# rpm.net
KiCad netlist of a schematic drawn in Altium Designer
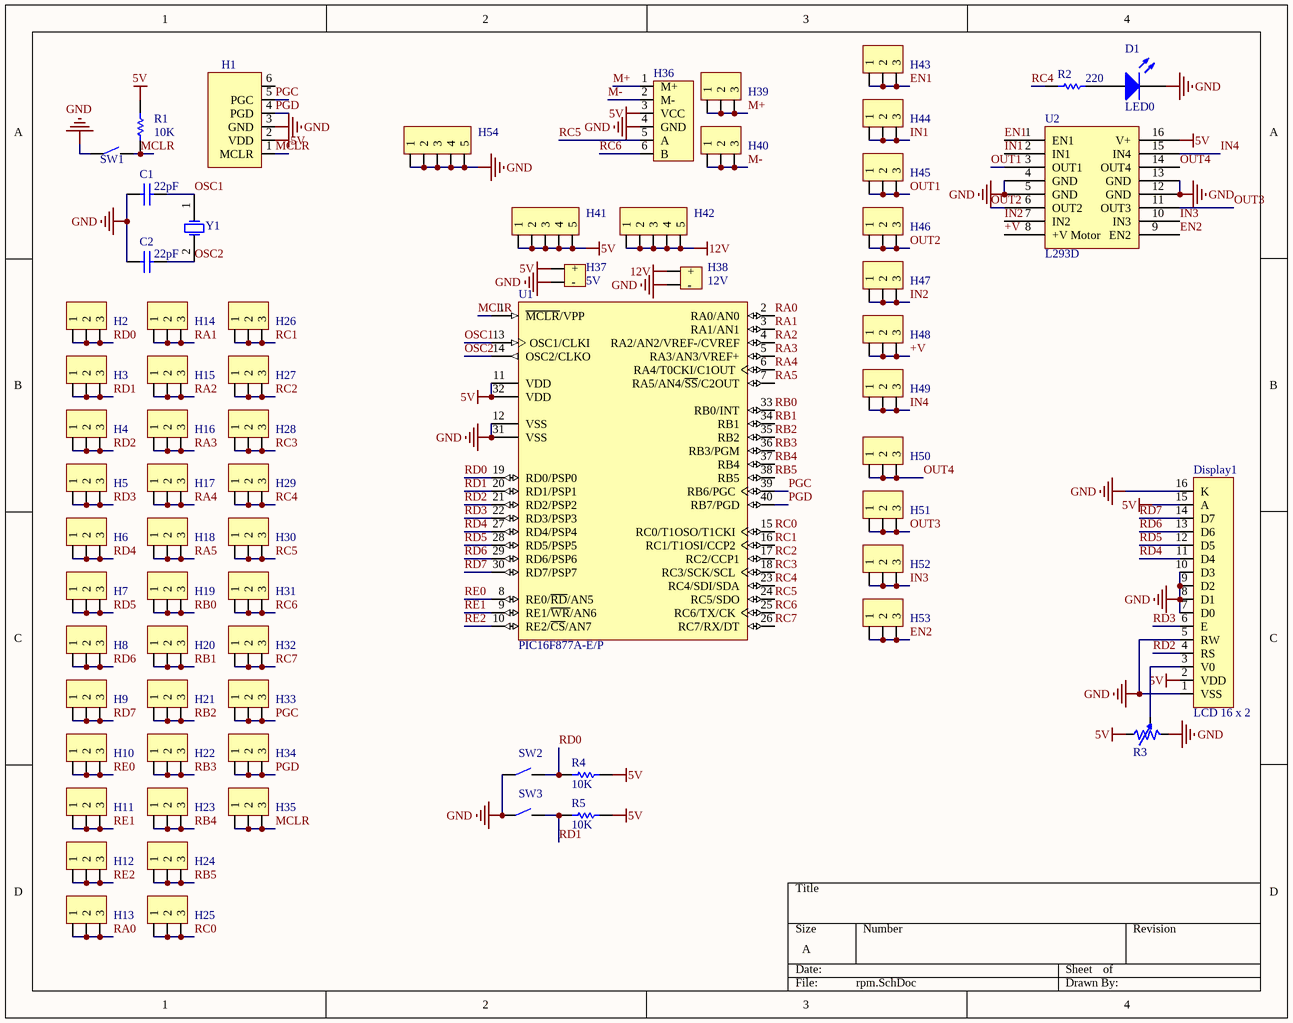
[diagram p0: rpm.SchDoc]

(export (version "E")
  (design (tool "Eeschema 10.0.6"))
  (components
    (comp (ref "C1")
      (value "22pF")
      (footprint "RAD-0.3")
      (description "Capacitor")
      (fields (field (name "Comment") "Cap") (field (name "PUBLISHER") "Altium Limited"))
      (libsource (lib "Miscellaneous Devices") (part "Cap"))
    )
    (comp (ref "C2")
      (value "22pF")
      (footprint "RAD-0.3")
      (description "Capacitor")
      (fields (field (name "Comment") "Cap") (field (name "PUBLISHER") "Altium Limited"))
      (libsource (lib "Miscellaneous Devices") (part "Cap"))
    )
    (comp (ref "D1")
      (value "LED0")
      (footprint "LED-0")
      (description "Typical INFRARED GaAs LED")
      (fields (field (name "PUBLISHER") "Altium Limited"))
      (libsource (lib "Miscellaneous Devices") (part "LED0"))
    )
    (comp (ref "Display1")
      (value "LCD 16 x 2")
      (footprint "LCD16x2")
      (libsource (lib "Konektori") (part "LCD 16 X 2"))
    )
    (comp (ref "H1") (value "Programmer") (footprint "Pickit") (libsource (lib "Konektori") (part "PICKIT")))
    (comp (ref "H2")
      (value "Comment")
      (footprint "1X3 HEADER")
      (libsource (lib "Konektori") (part "1X3 Header"))
    )
    (comp (ref "H3")
      (value "Comment")
      (footprint "1X3 HEADER")
      (libsource (lib "Konektori") (part "1X3 Header"))
    )
    (comp (ref "H4")
      (value "Comment")
      (footprint "1X3 HEADER")
      (libsource (lib "Konektori") (part "1X3 Header"))
    )
    (comp (ref "H5")
      (value "Comment")
      (footprint "1X3 HEADER")
      (libsource (lib "Konektori") (part "1X3 Header"))
    )
    (comp (ref "H6")
      (value "Comment")
      (footprint "1X3 HEADER")
      (libsource (lib "Konektori") (part "1X3 Header"))
    )
    (comp (ref "H7")
      (value "Comment")
      (footprint "1X3 HEADER")
      (libsource (lib "Konektori") (part "1X3 Header"))
    )
    (comp (ref "H8")
      (value "Comment")
      (footprint "1X3 HEADER")
      (libsource (lib "Konektori") (part "1X3 Header"))
    )
    (comp (ref "H9")
      (value "Comment")
      (footprint "1X3 HEADER")
      (libsource (lib "Konektori") (part "1X3 Header"))
    )
    (comp (ref "H10")
      (value "Comment")
      (footprint "1X3 HEADER")
      (libsource (lib "Konektori") (part "1X3 Header"))
    )
    (comp (ref "H11")
      (value "Comment")
      (footprint "1X3 HEADER")
      (libsource (lib "Konektori") (part "1X3 Header"))
    )
    (comp (ref "H12")
      (value "Comment")
      (footprint "1X3 HEADER")
      (libsource (lib "Konektori") (part "1X3 Header"))
    )
    (comp (ref "H13")
      (value "Comment")
      (footprint "1X3 HEADER")
      (libsource (lib "Konektori") (part "1X3 Header"))
    )
    (comp (ref "H14")
      (value "Comment")
      (footprint "1X3 HEADER")
      (libsource (lib "Konektori") (part "1X3 Header"))
    )
    (comp (ref "H15")
      (value "Comment")
      (footprint "1X3 HEADER")
      (libsource (lib "Konektori") (part "1X3 Header"))
    )
    (comp (ref "H16")
      (value "Comment")
      (footprint "1X3 HEADER")
      (libsource (lib "Konektori") (part "1X3 Header"))
    )
    (comp (ref "H17")
      (value "Comment")
      (footprint "1X3 HEADER")
      (libsource (lib "Konektori") (part "1X3 Header"))
    )
    (comp (ref "H18")
      (value "Comment")
      (footprint "1X3 HEADER")
      (libsource (lib "Konektori") (part "1X3 Header"))
    )
    (comp (ref "H19")
      (value "Comment")
      (footprint "1X3 HEADER")
      (libsource (lib "Konektori") (part "1X3 Header"))
    )
    (comp (ref "H20")
      (value "Comment")
      (footprint "1X3 HEADER")
      (libsource (lib "Konektori") (part "1X3 Header"))
    )
    (comp (ref "H21")
      (value "Comment")
      (footprint "1X3 HEADER")
      (libsource (lib "Konektori") (part "1X3 Header"))
    )
    (comp (ref "H22")
      (value "Comment")
      (footprint "1X3 HEADER")
      (libsource (lib "Konektori") (part "1X3 Header"))
    )
    (comp (ref "H23")
      (value "Comment")
      (footprint "1X3 HEADER")
      (libsource (lib "Konektori") (part "1X3 Header"))
    )
    (comp (ref "H24")
      (value "Comment")
      (footprint "1X3 HEADER")
      (libsource (lib "Konektori") (part "1X3 Header"))
    )
    (comp (ref "H25")
      (value "Comment")
      (footprint "1X3 HEADER")
      (libsource (lib "Konektori") (part "1X3 Header"))
    )
    (comp (ref "H26")
      (value "Comment")
      (footprint "1X3 HEADER")
      (libsource (lib "Konektori") (part "1X3 Header"))
    )
    (comp (ref "H27")
      (value "Comment")
      (footprint "1X3 HEADER")
      (libsource (lib "Konektori") (part "1X3 Header"))
    )
    (comp (ref "H28")
      (value "Comment")
      (footprint "1X3 HEADER")
      (libsource (lib "Konektori") (part "1X3 Header"))
    )
    (comp (ref "H29")
      (value "Comment")
      (footprint "1X3 HEADER")
      (libsource (lib "Konektori") (part "1X3 Header"))
    )
    (comp (ref "H30")
      (value "Comment")
      (footprint "1X3 HEADER")
      (libsource (lib "Konektori") (part "1X3 Header"))
    )
    (comp (ref "H31")
      (value "Comment")
      (footprint "1X3 HEADER")
      (libsource (lib "Konektori") (part "1X3 Header"))
    )
    (comp (ref "H32")
      (value "Comment")
      (footprint "1X3 HEADER")
      (libsource (lib "Konektori") (part "1X3 Header"))
    )
    (comp (ref "H33")
      (value "Comment")
      (footprint "1X3 HEADER")
      (libsource (lib "Konektori") (part "1X3 Header"))
    )
    (comp (ref "H34")
      (value "Comment")
      (footprint "1X3 HEADER")
      (libsource (lib "Konektori") (part "1X3 Header"))
    )
    (comp (ref "H35")
      (value "Comment")
      (footprint "1X3 HEADER")
      (libsource (lib "Konektori") (part "1X3 Header"))
    )
    (comp (ref "H36")
      (value "Comment")
      (footprint "MOTOR ENCODER BLUE SCREW")
      (libsource (lib "Konektori") (part "Motor encoder blue screw"))
    )
    (comp (ref "H37")
      (value "5V")
      (footprint "1x2 Voltage blue screw")
      (libsource (lib "Konektori") (part "1x2 Voltage blue screw"))
    )
    (comp (ref "H38")
      (value "12V")
      (footprint "1x2 Voltage blue screw")
      (libsource (lib "Konektori") (part "1x2 Voltage blue screw"))
    )
    (comp (ref "H39")
      (value "Comment")
      (footprint "1X3 HEADER")
      (libsource (lib "Konektori") (part "1X3 Header"))
    )
    (comp (ref "H40")
      (value "Comment")
      (footprint "1X3 HEADER")
      (libsource (lib "Konektori") (part "1X3 Header"))
    )
    (comp (ref "H41")
      (value "Comment")
      (footprint "1X5 HEADER")
      (libsource (lib "Konektori") (part "1X5 Header"))
    )
    (comp (ref "H42")
      (value "Comment")
      (footprint "1X5 HEADER")
      (libsource (lib "Konektori") (part "1X5 Header"))
    )
    (comp (ref "H43")
      (value "Comment")
      (footprint "1X3 HEADER")
      (libsource (lib "Konektori") (part "1X3 Header"))
    )
    (comp (ref "H44")
      (value "Comment")
      (footprint "1X3 HEADER")
      (libsource (lib "Konektori") (part "1X3 Header"))
    )
    (comp (ref "H45")
      (value "Comment")
      (footprint "1X3 HEADER")
      (libsource (lib "Konektori") (part "1X3 Header"))
    )
    (comp (ref "H46")
      (value "Comment")
      (footprint "1X3 HEADER")
      (libsource (lib "Konektori") (part "1X3 Header"))
    )
    (comp (ref "H47")
      (value "Comment")
      (footprint "1X3 HEADER")
      (libsource (lib "Konektori") (part "1X3 Header"))
    )
    (comp (ref "H48")
      (value "Comment")
      (footprint "1X3 HEADER")
      (libsource (lib "Konektori") (part "1X3 Header"))
    )
    (comp (ref "H49")
      (value "Comment")
      (footprint "1X3 HEADER")
      (libsource (lib "Konektori") (part "1X3 Header"))
    )
    (comp (ref "H50")
      (value "Comment")
      (footprint "1X3 HEADER")
      (libsource (lib "Konektori") (part "1X3 Header"))
    )
    (comp (ref "H51")
      (value "Comment")
      (footprint "1X3 HEADER")
      (libsource (lib "Konektori") (part "1X3 Header"))
    )
    (comp (ref "H52")
      (value "Comment")
      (footprint "1X3 HEADER")
      (libsource (lib "Konektori") (part "1X3 Header"))
    )
    (comp (ref "H53")
      (value "Comment")
      (footprint "1X3 HEADER")
      (libsource (lib "Konektori") (part "1X3 Header"))
    )
    (comp (ref "H54")
      (value "Comment")
      (footprint "1X5 HEADER")
      (libsource (lib "Konektori") (part "1X5 Header"))
    )
    (comp (ref "R1")
      (value "10K")
      (footprint "AXIAL-0.3")
      (description "Resistor")
      (fields (field (name "Comment") "Res1") (field (name "PUBLISHER") "Altium Limited"))
      (libsource (lib "Miscellaneous Devices") (part "Res1"))
    )
    (comp (ref "R2")
      (value "220")
      (footprint "AXIAL-0.3")
      (description "Resistor")
      (fields (field (name "Comment") "Res1") (field (name "PUBLISHER") "Altium Limited"))
      (libsource (lib "Miscellaneous Devices") (part "Res1"))
    )
    (comp (ref "R3")
      (value "Potenciometar")
      (footprint "ADJ_RES")
      (libsource (lib "Konektori") (part "ADJ_RES"))
    )
    (comp (ref "R4")
      (value "10K")
      (footprint "AXIAL-0.3")
      (description "Resistor")
      (fields (field (name "Comment") "Res1") (field (name "PUBLISHER") "Altium Limited"))
      (libsource (lib "Miscellaneous Devices") (part "Res1"))
    )
    (comp (ref "R5")
      (value "10K")
      (footprint "AXIAL-0.3")
      (description "Resistor")
      (fields (field (name "Comment") "Res1") (field (name "PUBLISHER") "Altium Limited"))
      (libsource (lib "Miscellaneous Devices") (part "Res1"))
    )
    (comp (ref "SW1")
      (value "Taster SMD")
      (footprint "Taster SMD")
      (fields (field (name "MP") "2-1437565-8") (field (name "MF") "TE Connectivity"))
      (libsource (lib "Tasters") (part "Taster SMD"))
    )
    (comp (ref "SW2")
      (value "Taster SMD")
      (footprint "Taster SMD")
      (fields (field (name "MP") "2-1437565-8") (field (name "MF") "TE Connectivity"))
      (libsource (lib "Tasters") (part "Taster SMD"))
    )
    (comp (ref "SW3")
      (value "Taster SMD")
      (footprint "Taster SMD")
      (fields (field (name "MP") "2-1437565-8") (field (name "MF") "TE Connectivity"))
      (libsource (lib "Tasters") (part "Taster SMD"))
    )
    (comp (ref "U1")
      (value "PIC16F877A-E/P")
      (footprint "PDIP600-P40")
      (fields (field (name "PUBLISHER") "Altium Limited"))
      (libsource (lib "Microchip Microcontroller 8-Bit PIC16") (part "PIC16F877A-E/P"))
    )
    (comp (ref "U2")
      (value "L293D")
      (footprint "L293D")
      (description "Motor Driver")
      (libsource (lib "Motor Drivers") (part "L293D"))
    )
    (comp (ref "Y1")
      (value "XTAL")
      (footprint "R38")
      (description "Crystal Oscillator")
      (fields (field (name "PUBLISHER") "Altium Limited"))
      (libsource (lib "Miscellaneous Devices") (part "XTAL"))
    )
  )
  (nets
    (net (code "1") (name "/+V") (class "Default")
      (node (ref "H48") (pin "1") (pinfunction "1_1") (pintype "passive"))
      (node (ref "H48") (pin "2") (pinfunction "2_2") (pintype "passive"))
      (node (ref "H48") (pin "3") (pinfunction "3_3") (pintype "passive"))
      (node (ref "U2") (pin "8") (pinfunction "+V_Motor_8") (pintype "passive"))
    )
    (net (code "2") (name "/EN1") (class "Default")
      (node (ref "H43") (pin "1") (pinfunction "1_1") (pintype "passive"))
      (node (ref "H43") (pin "2") (pinfunction "2_2") (pintype "passive"))
      (node (ref "H43") (pin "3") (pinfunction "3_3") (pintype "passive"))
      (node (ref "U2") (pin "1") (pinfunction "EN1_1") (pintype "passive"))
    )
    (net (code "3") (name "/EN2") (class "Default")
      (node (ref "H53") (pin "1") (pinfunction "1_1") (pintype "passive"))
      (node (ref "H53") (pin "2") (pinfunction "2_2") (pintype "passive"))
      (node (ref "H53") (pin "3") (pinfunction "3_3") (pintype "passive"))
      (node (ref "U2") (pin "9") (pinfunction "EN2_9") (pintype "passive"))
    )
    (net (code "4") (name "/IN1") (class "Default")
      (node (ref "H44") (pin "1") (pinfunction "1_1") (pintype "passive"))
      (node (ref "H44") (pin "2") (pinfunction "2_2") (pintype "passive"))
      (node (ref "H44") (pin "3") (pinfunction "3_3") (pintype "passive"))
      (node (ref "U2") (pin "2") (pinfunction "IN1_2") (pintype "passive"))
    )
    (net (code "5") (name "/IN2") (class "Default")
      (node (ref "H47") (pin "1") (pinfunction "1_1") (pintype "passive"))
      (node (ref "H47") (pin "2") (pinfunction "2_2") (pintype "passive"))
      (node (ref "H47") (pin "3") (pinfunction "3_3") (pintype "passive"))
      (node (ref "U2") (pin "7") (pinfunction "IN2_7") (pintype "passive"))
    )
    (net (code "6") (name "/IN3") (class "Default")
      (node (ref "H52") (pin "1") (pinfunction "1_1") (pintype "passive"))
      (node (ref "H52") (pin "2") (pinfunction "2_2") (pintype "passive"))
      (node (ref "H52") (pin "3") (pinfunction "3_3") (pintype "passive"))
      (node (ref "U2") (pin "10") (pinfunction "IN3_10") (pintype "passive"))
    )
    (net (code "7") (name "/IN4") (class "Default")
      (node (ref "H49") (pin "1") (pinfunction "1_1") (pintype "passive"))
      (node (ref "H49") (pin "2") (pinfunction "2_2") (pintype "passive"))
      (node (ref "H49") (pin "3") (pinfunction "3_3") (pintype "passive"))
      (node (ref "U2") (pin "15") (pinfunction "IN4_15") (pintype "passive"))
    )
    (net (code "8") (name "/M+") (class "Default")
      (node (ref "H36") (pin "1") (pinfunction "M+_1") (pintype "passive"))
      (node (ref "H39") (pin "1") (pinfunction "1_1") (pintype "passive"))
      (node (ref "H39") (pin "2") (pinfunction "2_2") (pintype "passive"))
      (node (ref "H39") (pin "3") (pinfunction "3_3") (pintype "passive"))
    )
    (net (code "9") (name "/M-") (class "Default")
      (node (ref "H36") (pin "2") (pinfunction "M-_2") (pintype "passive"))
      (node (ref "H40") (pin "1") (pinfunction "1_1") (pintype "passive"))
      (node (ref "H40") (pin "2") (pinfunction "2_2") (pintype "passive"))
      (node (ref "H40") (pin "3") (pinfunction "3_3") (pintype "passive"))
    )
    (net (code "10") (name "/MCLR") (class "Default")
      (node (ref "H1") (pin "1") (pinfunction "MCLR_1") (pintype "passive"))
      (node (ref "H35") (pin "1") (pinfunction "1_1") (pintype "passive"))
      (node (ref "H35") (pin "2") (pinfunction "2_2") (pintype "passive"))
      (node (ref "H35") (pin "3") (pinfunction "3_3") (pintype "passive"))
      (node (ref "R1") (pin "2") (pinfunction "2_2") (pintype "passive"))
      (node (ref "SW1") (pin "2") (pinfunction "2_2") (pintype "passive"))
      (node (ref "U1") (pin "1") (pinfunction "~{MCLR}/VPP_1") (pintype "input"))
    )
    (net (code "11") (name "/OSC1") (class "Default")
      (node (ref "C1") (pin "2") (pinfunction "2_2") (pintype "passive"))
      (node (ref "U1") (pin "13") (pinfunction "OSC1/CLKI_13") (pintype "input"))
      (node (ref "Y1") (pin "1") (pinfunction "OSC1_1") (pintype "passive"))
    )
    (net (code "12") (name "/OSC2") (class "Default")
      (node (ref "C2") (pin "2") (pinfunction "2_2") (pintype "passive"))
      (node (ref "U1") (pin "14") (pinfunction "OSC2/CLKO_14") (pintype "output"))
      (node (ref "Y1") (pin "2") (pinfunction "OSC2_2") (pintype "passive"))
    )
    (net (code "13") (name "/OUT1") (class "Default")
      (node (ref "H45") (pin "1") (pinfunction "1_1") (pintype "passive"))
      (node (ref "H45") (pin "2") (pinfunction "2_2") (pintype "passive"))
      (node (ref "H45") (pin "3") (pinfunction "3_3") (pintype "passive"))
      (node (ref "U2") (pin "3") (pinfunction "OUT1_3") (pintype "passive"))
    )
    (net (code "14") (name "/OUT2") (class "Default")
      (node (ref "H46") (pin "1") (pinfunction "1_1") (pintype "passive"))
      (node (ref "H46") (pin "2") (pinfunction "2_2") (pintype "passive"))
      (node (ref "H46") (pin "3") (pinfunction "3_3") (pintype "passive"))
      (node (ref "U2") (pin "6") (pinfunction "OUT2_6") (pintype "passive"))
    )
    (net (code "15") (name "/OUT3") (class "Default")
      (node (ref "H51") (pin "1") (pinfunction "1_1") (pintype "passive"))
      (node (ref "H51") (pin "2") (pinfunction "2_2") (pintype "passive"))
      (node (ref "H51") (pin "3") (pinfunction "3_3") (pintype "passive"))
      (node (ref "U2") (pin "11") (pinfunction "OUT3_11") (pintype "passive"))
    )
    (net (code "16") (name "/OUT4") (class "Default")
      (node (ref "H50") (pin "1") (pinfunction "1_1") (pintype "passive"))
      (node (ref "H50") (pin "2") (pinfunction "2_2") (pintype "passive"))
      (node (ref "H50") (pin "3") (pinfunction "3_3") (pintype "passive"))
      (node (ref "U2") (pin "14") (pinfunction "OUT4_14") (pintype "passive"))
    )
    (net (code "17") (name "/PGC") (class "Default")
      (node (ref "H1") (pin "5") (pinfunction "PGC_5") (pintype "passive"))
      (node (ref "H33") (pin "1") (pinfunction "1_1") (pintype "passive"))
      (node (ref "H33") (pin "2") (pinfunction "2_2") (pintype "passive"))
      (node (ref "H33") (pin "3") (pinfunction "3_3") (pintype "passive"))
      (node (ref "U1") (pin "39") (pinfunction "RB6/PGC_39") (pintype "bidirectional"))
    )
    (net (code "18") (name "/PGD") (class "Default")
      (node (ref "H1") (pin "4") (pinfunction "PGD_4") (pintype "passive"))
      (node (ref "H34") (pin "1") (pinfunction "1_1") (pintype "passive"))
      (node (ref "H34") (pin "2") (pinfunction "2_2") (pintype "passive"))
      (node (ref "H34") (pin "3") (pinfunction "3_3") (pintype "passive"))
      (node (ref "U1") (pin "40") (pinfunction "RB7/PGD_40") (pintype "bidirectional"))
    )
    (net (code "19") (name "/RA0") (class "Default")
      (node (ref "H13") (pin "1") (pinfunction "1_1") (pintype "passive"))
      (node (ref "H13") (pin "2") (pinfunction "2_2") (pintype "passive"))
      (node (ref "H13") (pin "3") (pinfunction "3_3") (pintype "passive"))
      (node (ref "U1") (pin "2") (pinfunction "RA0/AN0_2") (pintype "bidirectional"))
    )
    (net (code "20") (name "/RA1") (class "Default")
      (node (ref "H14") (pin "1") (pinfunction "1_1") (pintype "passive"))
      (node (ref "H14") (pin "2") (pinfunction "2_2") (pintype "passive"))
      (node (ref "H14") (pin "3") (pinfunction "3_3") (pintype "passive"))
      (node (ref "U1") (pin "3") (pinfunction "RA1/AN1_3") (pintype "bidirectional"))
    )
    (net (code "21") (name "/RA2") (class "Default")
      (node (ref "H15") (pin "1") (pinfunction "1_1") (pintype "passive"))
      (node (ref "H15") (pin "2") (pinfunction "2_2") (pintype "passive"))
      (node (ref "H15") (pin "3") (pinfunction "3_3") (pintype "passive"))
      (node (ref "U1") (pin "4") (pinfunction "RA2/AN2/VREF-/CVREF_4") (pintype "bidirectional"))
    )
    (net (code "22") (name "/RA3") (class "Default")
      (node (ref "H16") (pin "1") (pinfunction "1_1") (pintype "passive"))
      (node (ref "H16") (pin "2") (pinfunction "2_2") (pintype "passive"))
      (node (ref "H16") (pin "3") (pinfunction "3_3") (pintype "passive"))
      (node (ref "U1") (pin "5") (pinfunction "RA3/AN3/VREF+_5") (pintype "bidirectional"))
    )
    (net (code "23") (name "/RA4") (class "Default")
      (node (ref "H17") (pin "1") (pinfunction "1_1") (pintype "passive"))
      (node (ref "H17") (pin "2") (pinfunction "2_2") (pintype "passive"))
      (node (ref "H17") (pin "3") (pinfunction "3_3") (pintype "passive"))
      (node (ref "U1") (pin "6") (pinfunction "RA4/T0CKI/C1OUT_6") (pintype "bidirectional"))
    )
    (net (code "24") (name "/RA5") (class "Default")
      (node (ref "H18") (pin "1") (pinfunction "1_1") (pintype "passive"))
      (node (ref "H18") (pin "2") (pinfunction "2_2") (pintype "passive"))
      (node (ref "H18") (pin "3") (pinfunction "3_3") (pintype "passive"))
      (node (ref "U1") (pin "7") (pinfunction "RA5/AN4/~{SS}/C2OUT_7") (pintype "bidirectional"))
    )
    (net (code "25") (name "/RB0") (class "Default")
      (node (ref "H19") (pin "1") (pinfunction "1_1") (pintype "passive"))
      (node (ref "H19") (pin "2") (pinfunction "2_2") (pintype "passive"))
      (node (ref "H19") (pin "3") (pinfunction "3_3") (pintype "passive"))
      (node (ref "U1") (pin "33") (pinfunction "RB0/INT_33") (pintype "bidirectional"))
    )
    (net (code "26") (name "/RB1") (class "Default")
      (node (ref "H20") (pin "1") (pinfunction "1_1") (pintype "passive"))
      (node (ref "H20") (pin "2") (pinfunction "2_2") (pintype "passive"))
      (node (ref "H20") (pin "3") (pinfunction "3_3") (pintype "passive"))
      (node (ref "U1") (pin "34") (pinfunction "RB1_34") (pintype "bidirectional"))
    )
    (net (code "27") (name "/RB2") (class "Default")
      (node (ref "H21") (pin "1") (pinfunction "1_1") (pintype "passive"))
      (node (ref "H21") (pin "2") (pinfunction "2_2") (pintype "passive"))
      (node (ref "H21") (pin "3") (pinfunction "3_3") (pintype "passive"))
      (node (ref "U1") (pin "35") (pinfunction "RB2_35") (pintype "bidirectional"))
    )
    (net (code "28") (name "/RB3") (class "Default")
      (node (ref "H22") (pin "1") (pinfunction "1_1") (pintype "passive"))
      (node (ref "H22") (pin "2") (pinfunction "2_2") (pintype "passive"))
      (node (ref "H22") (pin "3") (pinfunction "3_3") (pintype "passive"))
      (node (ref "U1") (pin "36") (pinfunction "RB3/PGM_36") (pintype "bidirectional"))
    )
    (net (code "29") (name "/RB4") (class "Default")
      (node (ref "H23") (pin "1") (pinfunction "1_1") (pintype "passive"))
      (node (ref "H23") (pin "2") (pinfunction "2_2") (pintype "passive"))
      (node (ref "H23") (pin "3") (pinfunction "3_3") (pintype "passive"))
      (node (ref "U1") (pin "37") (pinfunction "RB4_37") (pintype "bidirectional"))
    )
    (net (code "30") (name "/RB5") (class "Default")
      (node (ref "H24") (pin "1") (pinfunction "1_1") (pintype "passive"))
      (node (ref "H24") (pin "2") (pinfunction "2_2") (pintype "passive"))
      (node (ref "H24") (pin "3") (pinfunction "3_3") (pintype "passive"))
      (node (ref "U1") (pin "38") (pinfunction "RB5_38") (pintype "bidirectional"))
    )
    (net (code "31") (name "/RC0") (class "Default")
      (node (ref "H25") (pin "1") (pinfunction "1_1") (pintype "passive"))
      (node (ref "H25") (pin "2") (pinfunction "2_2") (pintype "passive"))
      (node (ref "H25") (pin "3") (pinfunction "3_3") (pintype "passive"))
      (node (ref "U1") (pin "15") (pinfunction "RC0/T1OSO/T1CKI_15") (pintype "bidirectional"))
    )
    (net (code "32") (name "/RC1") (class "Default")
      (node (ref "H26") (pin "1") (pinfunction "1_1") (pintype "passive"))
      (node (ref "H26") (pin "2") (pinfunction "2_2") (pintype "passive"))
      (node (ref "H26") (pin "3") (pinfunction "3_3") (pintype "passive"))
      (node (ref "U1") (pin "16") (pinfunction "RC1/T1OSI/CCP2_16") (pintype "bidirectional"))
    )
    (net (code "33") (name "/RC2") (class "Default")
      (node (ref "H27") (pin "1") (pinfunction "1_1") (pintype "passive"))
      (node (ref "H27") (pin "2") (pinfunction "2_2") (pintype "passive"))
      (node (ref "H27") (pin "3") (pinfunction "3_3") (pintype "passive"))
      (node (ref "U1") (pin "17") (pinfunction "RC2/CCP1_17") (pintype "bidirectional"))
    )
    (net (code "34") (name "/RC3") (class "Default")
      (node (ref "H28") (pin "1") (pinfunction "1_1") (pintype "passive"))
      (node (ref "H28") (pin "2") (pinfunction "2_2") (pintype "passive"))
      (node (ref "H28") (pin "3") (pinfunction "3_3") (pintype "passive"))
      (node (ref "U1") (pin "18") (pinfunction "RC3/SCK/SCL_18") (pintype "bidirectional"))
    )
    (net (code "35") (name "/RC4") (class "Default")
      (node (ref "H29") (pin "1") (pinfunction "1_1") (pintype "passive"))
      (node (ref "H29") (pin "2") (pinfunction "2_2") (pintype "passive"))
      (node (ref "H29") (pin "3") (pinfunction "3_3") (pintype "passive"))
      (node (ref "R2") (pin "1") (pinfunction "1_1") (pintype "passive"))
      (node (ref "U1") (pin "23") (pinfunction "RC4/SDI/SDA_23") (pintype "bidirectional"))
    )
    (net (code "36") (name "/RC5") (class "Default")
      (node (ref "H30") (pin "1") (pinfunction "1_1") (pintype "passive"))
      (node (ref "H30") (pin "2") (pinfunction "2_2") (pintype "passive"))
      (node (ref "H30") (pin "3") (pinfunction "3_3") (pintype "passive"))
      (node (ref "H36") (pin "5") (pinfunction "A_5") (pintype "passive"))
      (node (ref "U1") (pin "24") (pinfunction "RC5/SDO_24") (pintype "bidirectional"))
    )
    (net (code "37") (name "/RC6") (class "Default")
      (node (ref "H31") (pin "1") (pinfunction "1_1") (pintype "passive"))
      (node (ref "H31") (pin "2") (pinfunction "2_2") (pintype "passive"))
      (node (ref "H31") (pin "3") (pinfunction "3_3") (pintype "passive"))
      (node (ref "H36") (pin "6") (pinfunction "B_6") (pintype "passive"))
      (node (ref "U1") (pin "25") (pinfunction "RC6/TX/CK_25") (pintype "bidirectional"))
    )
    (net (code "38") (name "/RC7") (class "Default")
      (node (ref "H32") (pin "1") (pinfunction "1_1") (pintype "passive"))
      (node (ref "H32") (pin "2") (pinfunction "2_2") (pintype "passive"))
      (node (ref "H32") (pin "3") (pinfunction "3_3") (pintype "passive"))
      (node (ref "U1") (pin "26") (pinfunction "RC7/RX/DT_26") (pintype "bidirectional"))
    )
    (net (code "39") (name "/RD0") (class "Default")
      (node (ref "H2") (pin "1") (pinfunction "1_1") (pintype "passive"))
      (node (ref "H2") (pin "2") (pinfunction "2_2") (pintype "passive"))
      (node (ref "H2") (pin "3") (pinfunction "3_3") (pintype "passive"))
      (node (ref "R4") (pin "2") (pinfunction "2_2") (pintype "passive"))
      (node (ref "SW2") (pin "2") (pinfunction "2_2") (pintype "passive"))
      (node (ref "U1") (pin "19") (pinfunction "RD0/PSP0_19") (pintype "bidirectional"))
    )
    (net (code "40") (name "/RD1") (class "Default")
      (node (ref "H3") (pin "1") (pinfunction "1_1") (pintype "passive"))
      (node (ref "H3") (pin "2") (pinfunction "2_2") (pintype "passive"))
      (node (ref "H3") (pin "3") (pinfunction "3_3") (pintype "passive"))
      (node (ref "R5") (pin "1") (pinfunction "1_1") (pintype "passive"))
      (node (ref "SW3") (pin "2") (pinfunction "2_2") (pintype "passive"))
      (node (ref "U1") (pin "20") (pinfunction "RD1/PSP1_20") (pintype "bidirectional"))
    )
    (net (code "41") (name "/RD2") (class "Default")
      (node (ref "Display1") (pin "4") (pinfunction "RS_4") (pintype "passive"))
      (node (ref "H4") (pin "1") (pinfunction "1_1") (pintype "passive"))
      (node (ref "H4") (pin "2") (pinfunction "2_2") (pintype "passive"))
      (node (ref "H4") (pin "3") (pinfunction "3_3") (pintype "passive"))
      (node (ref "U1") (pin "21") (pinfunction "RD2/PSP2_21") (pintype "bidirectional"))
    )
    (net (code "42") (name "/RD3") (class "Default")
      (node (ref "Display1") (pin "6") (pinfunction "E_6") (pintype "passive"))
      (node (ref "H5") (pin "1") (pinfunction "1_1") (pintype "passive"))
      (node (ref "H5") (pin "2") (pinfunction "2_2") (pintype "passive"))
      (node (ref "H5") (pin "3") (pinfunction "3_3") (pintype "passive"))
      (node (ref "U1") (pin "22") (pinfunction "RD3/PSP3_22") (pintype "bidirectional"))
    )
    (net (code "43") (name "/RD4") (class "Default")
      (node (ref "Display1") (pin "11") (pinfunction "D4_11") (pintype "passive"))
      (node (ref "H6") (pin "1") (pinfunction "1_1") (pintype "passive"))
      (node (ref "H6") (pin "2") (pinfunction "2_2") (pintype "passive"))
      (node (ref "H6") (pin "3") (pinfunction "3_3") (pintype "passive"))
      (node (ref "U1") (pin "27") (pinfunction "RD4/PSP4_27") (pintype "bidirectional"))
    )
    (net (code "44") (name "/RD5") (class "Default")
      (node (ref "Display1") (pin "12") (pinfunction "D5_12") (pintype "passive"))
      (node (ref "H7") (pin "1") (pinfunction "1_1") (pintype "passive"))
      (node (ref "H7") (pin "2") (pinfunction "2_2") (pintype "passive"))
      (node (ref "H7") (pin "3") (pinfunction "3_3") (pintype "passive"))
      (node (ref "U1") (pin "28") (pinfunction "RD5/PSP5_28") (pintype "bidirectional"))
    )
    (net (code "45") (name "/RD6") (class "Default")
      (node (ref "Display1") (pin "13") (pinfunction "D6_13") (pintype "passive"))
      (node (ref "H8") (pin "1") (pinfunction "1_1") (pintype "passive"))
      (node (ref "H8") (pin "2") (pinfunction "2_2") (pintype "passive"))
      (node (ref "H8") (pin "3") (pinfunction "3_3") (pintype "passive"))
      (node (ref "U1") (pin "29") (pinfunction "RD6/PSP6_29") (pintype "bidirectional"))
    )
    (net (code "46") (name "/RD7") (class "Default")
      (node (ref "Display1") (pin "14") (pinfunction "D7_14") (pintype "passive"))
      (node (ref "H9") (pin "1") (pinfunction "1_1") (pintype "passive"))
      (node (ref "H9") (pin "2") (pinfunction "2_2") (pintype "passive"))
      (node (ref "H9") (pin "3") (pinfunction "3_3") (pintype "passive"))
      (node (ref "U1") (pin "30") (pinfunction "RD7/PSP7_30") (pintype "bidirectional"))
    )
    (net (code "47") (name "/RE0") (class "Default")
      (node (ref "H10") (pin "1") (pinfunction "1_1") (pintype "passive"))
      (node (ref "H10") (pin "2") (pinfunction "2_2") (pintype "passive"))
      (node (ref "H10") (pin "3") (pinfunction "3_3") (pintype "passive"))
      (node (ref "U1") (pin "8") (pinfunction "RE0/~{RD}/AN5_8") (pintype "bidirectional"))
    )
    (net (code "48") (name "/RE1") (class "Default")
      (node (ref "H11") (pin "1") (pinfunction "1_1") (pintype "passive"))
      (node (ref "H11") (pin "2") (pinfunction "2_2") (pintype "passive"))
      (node (ref "H11") (pin "3") (pinfunction "3_3") (pintype "passive"))
      (node (ref "U1") (pin "9") (pinfunction "RE1/~{WR}/AN6_9") (pintype "bidirectional"))
    )
    (net (code "49") (name "/RE2") (class "Default")
      (node (ref "H12") (pin "1") (pinfunction "1_1") (pintype "passive"))
      (node (ref "H12") (pin "2") (pinfunction "2_2") (pintype "passive"))
      (node (ref "H12") (pin "3") (pinfunction "3_3") (pintype "passive"))
      (node (ref "U1") (pin "10") (pinfunction "RE2/~{CS}/AN7_10") (pintype "bidirectional"))
    )
    (net (code "50") (name "5V") (class "Default")
      (node (ref "Display1") (pin "15") (pinfunction "A_15") (pintype "passive"))
      (node (ref "Display1") (pin "2") (pinfunction "VDD_2") (pintype "passive"))
      (node (ref "H1") (pin "2") (pinfunction "VDD_2") (pintype "passive"))
      (node (ref "H36") (pin "3") (pinfunction "VCC_3") (pintype "passive"))
      (node (ref "H37") (pin "1") (pinfunction "+_1") (pintype "passive"))
      (node (ref "H41") (pin "1") (pinfunction "1_1") (pintype "passive"))
      (node (ref "H41") (pin "2") (pinfunction "2_2") (pintype "passive"))
      (node (ref "H41") (pin "3") (pinfunction "3_3") (pintype "passive"))
      (node (ref "H41") (pin "4") (pinfunction "4_4") (pintype "passive"))
      (node (ref "H41") (pin "5") (pinfunction "5_5") (pintype "passive"))
      (node (ref "R1") (pin "1") (pinfunction "1_1") (pintype "passive"))
      (node (ref "R3") (pin "1") (pinfunction "1_1") (pintype "passive"))
      (node (ref "R4") (pin "1") (pinfunction "1_1") (pintype "passive"))
      (node (ref "R5") (pin "2") (pinfunction "2_2") (pintype "passive"))
      (node (ref "U1") (pin "11") (pinfunction "VDD_11") (pintype "power_in"))
      (node (ref "U1") (pin "32") (pinfunction "VDD_32") (pintype "power_in"))
      (node (ref "U2") (pin "16") (pinfunction "V+_16") (pintype "passive"))
    )
    (net (code "51") (name "12V") (class "Default")
      (node (ref "H38") (pin "1") (pinfunction "+_1") (pintype "passive"))
      (node (ref "H42") (pin "1") (pinfunction "1_1") (pintype "passive"))
      (node (ref "H42") (pin "2") (pinfunction "2_2") (pintype "passive"))
      (node (ref "H42") (pin "3") (pinfunction "3_3") (pintype "passive"))
      (node (ref "H42") (pin "4") (pinfunction "4_4") (pintype "passive"))
      (node (ref "H42") (pin "5") (pinfunction "5_5") (pintype "passive"))
    )
    (net (code "52") (name "GND") (class "Default")
      (node (ref "C1") (pin "1") (pinfunction "1_1") (pintype "passive"))
      (node (ref "C2") (pin "1") (pinfunction "1_1") (pintype "passive"))
      (node (ref "D1") (pin "2") (pinfunction "K_2") (pintype "passive"))
      (node (ref "Display1") (pin "1") (pinfunction "VSS_1") (pintype "passive"))
      (node (ref "Display1") (pin "10") (pinfunction "D3_10") (pintype "passive"))
      (node (ref "Display1") (pin "16") (pinfunction "K_16") (pintype "passive"))
      (node (ref "Display1") (pin "5") (pinfunction "RW_5") (pintype "passive"))
      (node (ref "Display1") (pin "7") (pinfunction "D0_7") (pintype "passive"))
      (node (ref "Display1") (pin "8") (pinfunction "D1_8") (pintype "passive"))
      (node (ref "Display1") (pin "9") (pinfunction "D2_9") (pintype "passive"))
      (node (ref "H1") (pin "3") (pinfunction "GND_3") (pintype "passive"))
      (node (ref "H36") (pin "4") (pinfunction "GND_4") (pintype "passive"))
      (node (ref "H37") (pin "2") (pinfunction "-_2") (pintype "passive"))
      (node (ref "H38") (pin "2") (pinfunction "-_2") (pintype "passive"))
      (node (ref "H54") (pin "1") (pinfunction "1_1") (pintype "passive"))
      (node (ref "H54") (pin "2") (pinfunction "2_2") (pintype "passive"))
      (node (ref "H54") (pin "3") (pinfunction "3_3") (pintype "passive"))
      (node (ref "H54") (pin "4") (pinfunction "4_4") (pintype "passive"))
      (node (ref "H54") (pin "5") (pinfunction "5_5") (pintype "passive"))
      (node (ref "R3") (pin "2") (pinfunction "2_2") (pintype "passive"))
      (node (ref "SW1") (pin "1") (pinfunction "1_1") (pintype "passive"))
      (node (ref "SW2") (pin "1") (pinfunction "1_1") (pintype "passive"))
      (node (ref "SW3") (pin "1") (pinfunction "1_1") (pintype "passive"))
      (node (ref "U1") (pin "12") (pinfunction "VSS_12") (pintype "power_in"))
      (node (ref "U1") (pin "31") (pinfunction "VSS_31") (pintype "power_in"))
      (node (ref "U2") (pin "12") (pinfunction "GND_12") (pintype "passive"))
      (node (ref "U2") (pin "13") (pinfunction "GND_13") (pintype "passive"))
      (node (ref "U2") (pin "4") (pinfunction "GND_4") (pintype "passive"))
      (node (ref "U2") (pin "5") (pinfunction "GND_5") (pintype "passive"))
    )
    (net (code "53") (name "Net-(D1-A)") (class "Default")
      (node (ref "D1") (pin "1") (pinfunction "A_1") (pintype "passive"))
      (node (ref "R2") (pin "2") (pinfunction "2_2") (pintype "passive"))
    )
    (net (code "54") (name "Net-(Display1-V0)") (class "Default")
      (node (ref "Display1") (pin "3") (pinfunction "V0_3") (pintype "passive"))
      (node (ref "R3") (pin "3") (pinfunction "3_3") (pintype "passive"))
    )
    (net (code "55") (name "unconnected-(H1-Pad6)") (class "Default")
      (node (ref "H1") (pin "6") (pintype "passive"))
    )
  )
)
